# wifi_r3-esp_wr02.net
KiCad netlist of a schematic drawn in EAGLE
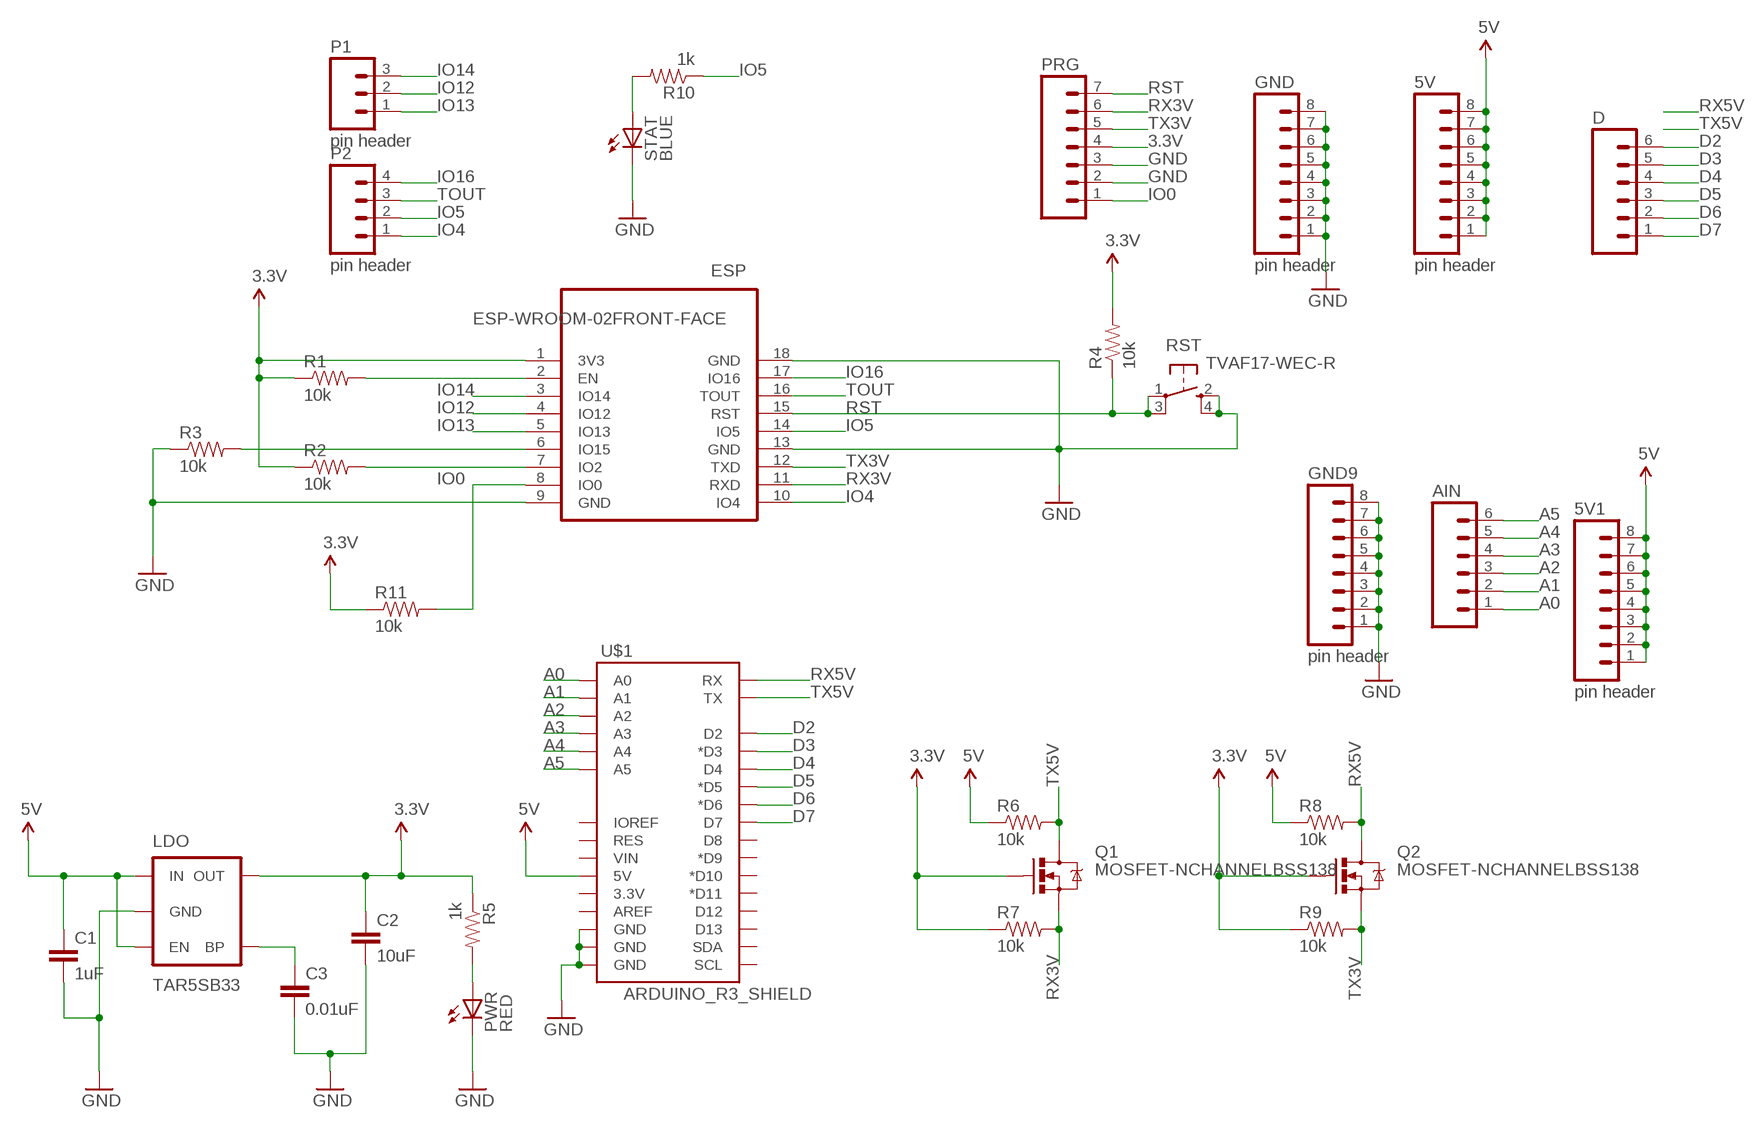
[diagram p0: schematic, sheet 1]

(export (version "E")
  (design (tool "Eeschema 10.0.6"))
  (components
    (comp (ref "5V")
      (value "pin header")
      (footprint "eagle-import:1X08")
      (libsource (lib "eagle-import") (part "M081X08"))
    )
    (comp (ref "5V1")
      (value "pin header")
      (footprint "eagle-import:1X08")
      (libsource (lib "eagle-import") (part "M081X08"))
    )
    (comp (ref "AIN")
      (value "M06SIP")
      (footprint "eagle-import:1X06")
      (libsource (lib "eagle-import") (part "M06SIP"))
    )
    (comp (ref "C1")
      (value "1uF")
      (footprint "eagle-import:0603-CAP")
      (libsource (lib "eagle-import") (part "CAP0603-CAP"))
    )
    (comp (ref "C2")
      (value "10uF")
      (footprint "eagle-import:0805")
      (libsource (lib "eagle-import") (part "CAP0805"))
    )
    (comp (ref "C3")
      (value "0.01uF")
      (footprint "eagle-import:0603-CAP")
      (libsource (lib "eagle-import") (part "CAP0603-CAP"))
    )
    (comp (ref "D")
      (value "M06SIP")
      (footprint "eagle-import:1X06")
      (libsource (lib "eagle-import") (part "M06SIP"))
    )
    (comp (ref "ESP")
      (value "ESP-WROOM-02FRONT-FACE")
      (footprint "eagle-import:FRONT-FACE")
      (libsource (lib "eagle-import") (part "ESP-WROOM-02FRONT-FACE"))
    )
    (comp (ref "GND")
      (value "pin header")
      (footprint "eagle-import:1X08")
      (libsource (lib "eagle-import") (part "M081X08"))
    )
    (comp (ref "GND9")
      (value "pin header")
      (footprint "eagle-import:1X08")
      (libsource (lib "eagle-import") (part "M081X08"))
    )
    (comp (ref "LDO")
      (value "TAR5SB33")
      (footprint "eagle-import:SOT23-5")
      (libsource (lib "eagle-import") (part "TAR5SB33"))
    )
    (comp (ref "P1")
      (value "pin header")
      (footprint "eagle-import:1X03")
      (libsource (lib "eagle-import") (part "M03PTH"))
    )
    (comp (ref "P2")
      (value "pin header")
      (footprint "eagle-import:1X04")
      (libsource (lib "eagle-import") (part "M04PTH"))
    )
    (comp (ref "PRG")
      (value "M07")
      (footprint "eagle-import:1X07")
      (libsource (lib "eagle-import") (part "M07"))
    )
    (comp (ref "PWR")
      (value "RED")
      (footprint "eagle-import:LED-0603")
      (libsource (lib "eagle-import") (part "LED0603"))
    )
    (comp (ref "Q1")
      (value "MOSFET-NCHANNELBSS138")
      (footprint "eagle-import:SOT23")
      (libsource (lib "eagle-import") (part "MOSFET-NCHANNELBSS138"))
    )
    (comp (ref "Q2")
      (value "MOSFET-NCHANNELBSS138")
      (footprint "eagle-import:SOT23")
      (libsource (lib "eagle-import") (part "MOSFET-NCHANNELBSS138"))
    )
    (comp (ref "R1")
      (value "10k")
      (footprint "eagle-import:0603-RES")
      (libsource (lib "eagle-import") (part "RESISTOR0603"))
    )
    (comp (ref "R2")
      (value "10k")
      (footprint "eagle-import:0603-RES")
      (libsource (lib "eagle-import") (part "RESISTOR0603"))
    )
    (comp (ref "R3")
      (value "10k")
      (footprint "eagle-import:0603-RES")
      (libsource (lib "eagle-import") (part "RESISTOR0603"))
    )
    (comp (ref "R4")
      (value "10k")
      (footprint "eagle-import:0603-RES")
      (libsource (lib "eagle-import") (part "RESISTOR0603"))
    )
    (comp (ref "R5")
      (value "1k")
      (footprint "eagle-import:0603-RES")
      (libsource (lib "eagle-import") (part "RESISTOR0603"))
    )
    (comp (ref "R6")
      (value "10k")
      (footprint "eagle-import:0603-RES")
      (libsource (lib "eagle-import") (part "RESISTOR0603"))
    )
    (comp (ref "R7")
      (value "10k")
      (footprint "eagle-import:0603-RES")
      (libsource (lib "eagle-import") (part "RESISTOR0603"))
    )
    (comp (ref "R8")
      (value "10k")
      (footprint "eagle-import:0603-RES")
      (libsource (lib "eagle-import") (part "RESISTOR0603"))
    )
    (comp (ref "R9")
      (value "10k")
      (footprint "eagle-import:0603-RES")
      (libsource (lib "eagle-import") (part "RESISTOR0603"))
    )
    (comp (ref "R10")
      (value "1k")
      (footprint "eagle-import:0603-RES")
      (libsource (lib "eagle-import") (part "RESISTOR0603"))
    )
    (comp (ref "R11")
      (value "10k")
      (footprint "eagle-import:0603-RES")
      (libsource (lib "eagle-import") (part "RESISTOR0603"))
    )
    (comp (ref "RST")
      (value "TVAF17-WEC-R")
      (footprint "eagle-import:KMR2")
      (libsource (lib "eagle-import") (part "SPST_TACT-KMR2"))
    )
    (comp (ref "STAT")
      (value "BLUE")
      (footprint "eagle-import:LED-0603")
      (libsource (lib "eagle-import") (part "LED0603"))
    )
    (comp (ref "U$1")
      (value "ARDUINO_R3_SHIELD")
      (footprint "eagle-import:UNO_R3_SHIELD")
      (libsource (lib "eagle-import") (part "ARDUINO_R3_SHIELD"))
    )
  )
  (nets
    (net (code "1") (name "/A0") (class "Default")
      (node (ref "AIN") (pin "1") (pinfunction "1_1") (pintype "passive"))
      (node (ref "U$1") (pin "A0") (pinfunction "A0_A0") (pintype "bidirectional"))
    )
    (net (code "2") (name "/A1") (class "Default")
      (node (ref "AIN") (pin "2") (pinfunction "2_2") (pintype "passive"))
      (node (ref "U$1") (pin "A1") (pinfunction "A1_A1") (pintype "bidirectional"))
    )
    (net (code "3") (name "/A2") (class "Default")
      (node (ref "AIN") (pin "3") (pinfunction "3_3") (pintype "passive"))
      (node (ref "U$1") (pin "A2") (pinfunction "A2_A2") (pintype "bidirectional"))
    )
    (net (code "4") (name "/A3") (class "Default")
      (node (ref "AIN") (pin "4") (pinfunction "4_4") (pintype "passive"))
      (node (ref "U$1") (pin "A3") (pinfunction "A3_A3") (pintype "bidirectional"))
    )
    (net (code "5") (name "/A4") (class "Default")
      (node (ref "AIN") (pin "5") (pinfunction "5_5") (pintype "passive"))
      (node (ref "U$1") (pin "A4") (pinfunction "A4_A4") (pintype "bidirectional"))
    )
    (net (code "6") (name "/A5") (class "Default")
      (node (ref "AIN") (pin "6") (pinfunction "6_6") (pintype "passive"))
      (node (ref "U$1") (pin "A5") (pinfunction "A5_A5") (pintype "bidirectional"))
    )
    (net (code "7") (name "/D2") (class "Default")
      (node (ref "D") (pin "6") (pinfunction "6_6") (pintype "passive"))
      (node (ref "U$1") (pin "D2") (pinfunction "D2_D2") (pintype "bidirectional"))
    )
    (net (code "8") (name "/D3") (class "Default")
      (node (ref "D") (pin "5") (pinfunction "5_5") (pintype "passive"))
      (node (ref "U$1") (pin "D3") (pinfunction "*D3_D3") (pintype "bidirectional"))
    )
    (net (code "9") (name "/D4") (class "Default")
      (node (ref "D") (pin "4") (pinfunction "4_4") (pintype "passive"))
      (node (ref "U$1") (pin "D4") (pinfunction "D4_D4") (pintype "bidirectional"))
    )
    (net (code "10") (name "/D5") (class "Default")
      (node (ref "D") (pin "3") (pinfunction "3_3") (pintype "passive"))
      (node (ref "U$1") (pin "D5") (pinfunction "*D5_D5") (pintype "bidirectional"))
    )
    (net (code "11") (name "/D6") (class "Default")
      (node (ref "D") (pin "2") (pinfunction "2_2") (pintype "passive"))
      (node (ref "U$1") (pin "D6") (pinfunction "*D6_D6") (pintype "bidirectional"))
    )
    (net (code "12") (name "/D7") (class "Default")
      (node (ref "D") (pin "1") (pinfunction "1_1") (pintype "passive"))
      (node (ref "U$1") (pin "D7") (pinfunction "D7_D7") (pintype "bidirectional"))
    )
    (net (code "13") (name "/IO0") (class "Default")
      (node (ref "ESP") (pin "8") (pinfunction "IO0_8") (pintype "bidirectional"))
      (node (ref "PRG") (pin "1") (pinfunction "1_1") (pintype "passive"))
      (node (ref "R11") (pin "2") (pinfunction "2_2") (pintype "passive"))
    )
    (net (code "14") (name "/IO4") (class "Default")
      (node (ref "ESP") (pin "10") (pinfunction "IO4_10") (pintype "bidirectional"))
      (node (ref "P2") (pin "1") (pinfunction "1_1") (pintype "passive"))
    )
    (net (code "15") (name "/IO5") (class "Default")
      (node (ref "ESP") (pin "14") (pinfunction "IO5_14") (pintype "open_collector"))
      (node (ref "P2") (pin "2") (pinfunction "2_2") (pintype "passive"))
      (node (ref "R10") (pin "1") (pinfunction "1_1") (pintype "passive"))
    )
    (net (code "16") (name "/IO12") (class "Default")
      (node (ref "ESP") (pin "4") (pinfunction "IO12_4") (pintype "bidirectional"))
      (node (ref "P1") (pin "2") (pinfunction "2_2") (pintype "passive"))
    )
    (net (code "17") (name "/IO13") (class "Default")
      (node (ref "ESP") (pin "5") (pinfunction "IO13_5") (pintype "bidirectional"))
      (node (ref "P1") (pin "1") (pinfunction "1_1") (pintype "passive"))
    )
    (net (code "18") (name "/IO14") (class "Default")
      (node (ref "ESP") (pin "3") (pinfunction "IO14_3") (pintype "bidirectional"))
      (node (ref "P1") (pin "3") (pinfunction "3_3") (pintype "passive"))
    )
    (net (code "19") (name "/IO16") (class "Default")
      (node (ref "ESP") (pin "17") (pinfunction "IO16_17") (pintype "bidirectional"))
      (node (ref "P2") (pin "4") (pinfunction "4_4") (pintype "passive"))
    )
    (net (code "20") (name "/RST") (class "Default")
      (node (ref "ESP") (pin "15") (pinfunction "RST_15") (pintype "bidirectional"))
      (node (ref "PRG") (pin "7") (pinfunction "7_7") (pintype "passive"))
      (node (ref "R4") (pin "1") (pinfunction "1_1") (pintype "passive"))
      (node (ref "RST") (pin "1") (pinfunction "P_1") (pintype "passive"))
      (node (ref "RST") (pin "3") (pinfunction "P_3") (pintype "passive"))
    )
    (net (code "21") (name "/RX3V") (class "Default")
      (node (ref "ESP") (pin "11") (pinfunction "RXD_11") (pintype "bidirectional"))
      (node (ref "PRG") (pin "6") (pinfunction "6_6") (pintype "passive"))
      (node (ref "Q1") (pin "2") (pinfunction "S_2") (pintype "passive"))
      (node (ref "R7") (pin "2") (pinfunction "2_2") (pintype "passive"))
    )
    (net (code "22") (name "/RX5V") (class "Default")
      (node (ref "Q2") (pin "3") (pinfunction "D_3") (pintype "passive"))
      (node (ref "R8") (pin "2") (pinfunction "2_2") (pintype "passive"))
      (node (ref "U$1") (pin "RX") (pinfunction "RX_RX") (pintype "bidirectional"))
    )
    (net (code "23") (name "/TOUT") (class "Default")
      (node (ref "ESP") (pin "16") (pinfunction "TOUT_16") (pintype "bidirectional"))
      (node (ref "P2") (pin "3") (pinfunction "3_3") (pintype "passive"))
    )
    (net (code "24") (name "/TX3V") (class "Default")
      (node (ref "ESP") (pin "12") (pinfunction "TXD_12") (pintype "bidirectional"))
      (node (ref "PRG") (pin "5") (pinfunction "5_5") (pintype "passive"))
      (node (ref "Q2") (pin "2") (pinfunction "S_2") (pintype "passive"))
      (node (ref "R9") (pin "2") (pinfunction "2_2") (pintype "passive"))
    )
    (net (code "25") (name "/TX5V") (class "Default")
      (node (ref "Q1") (pin "3") (pinfunction "D_3") (pintype "passive"))
      (node (ref "R6") (pin "2") (pinfunction "2_2") (pintype "passive"))
      (node (ref "U$1") (pin "TX") (pinfunction "TX_TX") (pintype "bidirectional"))
    )
    (net (code "26") (name "3.3V") (class "Default")
      (node (ref "C2") (pin "1") (pinfunction "1_1") (pintype "passive"))
      (node (ref "ESP") (pin "1") (pinfunction "3V3_1") (pintype "power_in"))
      (node (ref "LDO") (pin "5") (pinfunction "OUT_5") (pintype "passive"))
      (node (ref "PRG") (pin "4") (pinfunction "4_4") (pintype "passive"))
      (node (ref "Q1") (pin "1") (pinfunction "G_1") (pintype "passive"))
      (node (ref "Q2") (pin "1") (pinfunction "G_1") (pintype "passive"))
      (node (ref "R1") (pin "1") (pinfunction "1_1") (pintype "passive"))
      (node (ref "R11") (pin "1") (pinfunction "1_1") (pintype "passive"))
      (node (ref "R2") (pin "1") (pinfunction "1_1") (pintype "passive"))
      (node (ref "R4") (pin "2") (pinfunction "2_2") (pintype "passive"))
      (node (ref "R5") (pin "1") (pinfunction "1_1") (pintype "passive"))
      (node (ref "R7") (pin "1") (pinfunction "1_1") (pintype "passive"))
      (node (ref "R9") (pin "1") (pinfunction "1_1") (pintype "passive"))
    )
    (net (code "27") (name "5V") (class "Default")
      (node (ref "5V") (pin "1") (pinfunction "1_1") (pintype "passive"))
      (node (ref "5V") (pin "2") (pinfunction "2_2") (pintype "passive"))
      (node (ref "5V") (pin "3") (pinfunction "3_3") (pintype "passive"))
      (node (ref "5V") (pin "4") (pinfunction "4_4") (pintype "passive"))
      (node (ref "5V") (pin "5") (pinfunction "5_5") (pintype "passive"))
      (node (ref "5V") (pin "6") (pinfunction "6_6") (pintype "passive"))
      (node (ref "5V") (pin "7") (pinfunction "7_7") (pintype "passive"))
      (node (ref "5V") (pin "8") (pinfunction "8_8") (pintype "passive"))
      (node (ref "5V1") (pin "1") (pinfunction "1_1") (pintype "passive"))
      (node (ref "5V1") (pin "2") (pinfunction "2_2") (pintype "passive"))
      (node (ref "5V1") (pin "3") (pinfunction "3_3") (pintype "passive"))
      (node (ref "5V1") (pin "4") (pinfunction "4_4") (pintype "passive"))
      (node (ref "5V1") (pin "5") (pinfunction "5_5") (pintype "passive"))
      (node (ref "5V1") (pin "6") (pinfunction "6_6") (pintype "passive"))
      (node (ref "5V1") (pin "7") (pinfunction "7_7") (pintype "passive"))
      (node (ref "5V1") (pin "8") (pinfunction "8_8") (pintype "passive"))
      (node (ref "C1") (pin "1") (pinfunction "1_1") (pintype "passive"))
      (node (ref "LDO") (pin "1") (pinfunction "IN_1") (pintype "input"))
      (node (ref "LDO") (pin "3") (pinfunction "EN_3") (pintype "input"))
      (node (ref "R6") (pin "1") (pinfunction "1_1") (pintype "passive"))
      (node (ref "R8") (pin "1") (pinfunction "1_1") (pintype "passive"))
      (node (ref "U$1") (pin "5V") (pinfunction "5V_5V") (pintype "bidirectional"))
    )
    (net (code "28") (name "GND") (class "Default")
      (node (ref "C1") (pin "2") (pinfunction "2_2") (pintype "passive"))
      (node (ref "C2") (pin "2") (pinfunction "2_2") (pintype "passive"))
      (node (ref "C3") (pin "2") (pinfunction "2_2") (pintype "passive"))
      (node (ref "ESP") (pin "13") (pinfunction "GND_13") (pintype "power_in"))
      (node (ref "ESP") (pin "18") (pinfunction "GND_18") (pintype "power_in"))
      (node (ref "ESP") (pin "9") (pinfunction "GND_9") (pintype "power_in"))
      (node (ref "GND") (pin "1") (pinfunction "1_1") (pintype "passive"))
      (node (ref "GND") (pin "2") (pinfunction "2_2") (pintype "passive"))
      (node (ref "GND") (pin "3") (pinfunction "3_3") (pintype "passive"))
      (node (ref "GND") (pin "4") (pinfunction "4_4") (pintype "passive"))
      (node (ref "GND") (pin "5") (pinfunction "5_5") (pintype "passive"))
      (node (ref "GND") (pin "6") (pinfunction "6_6") (pintype "passive"))
      (node (ref "GND") (pin "7") (pinfunction "7_7") (pintype "passive"))
      (node (ref "GND") (pin "8") (pinfunction "8_8") (pintype "passive"))
      (node (ref "GND9") (pin "1") (pinfunction "1_1") (pintype "passive"))
      (node (ref "GND9") (pin "2") (pinfunction "2_2") (pintype "passive"))
      (node (ref "GND9") (pin "3") (pinfunction "3_3") (pintype "passive"))
      (node (ref "GND9") (pin "4") (pinfunction "4_4") (pintype "passive"))
      (node (ref "GND9") (pin "5") (pinfunction "5_5") (pintype "passive"))
      (node (ref "GND9") (pin "6") (pinfunction "6_6") (pintype "passive"))
      (node (ref "GND9") (pin "7") (pinfunction "7_7") (pintype "passive"))
      (node (ref "GND9") (pin "8") (pinfunction "8_8") (pintype "passive"))
      (node (ref "LDO") (pin "2") (pinfunction "GND_2") (pintype "input"))
      (node (ref "PRG") (pin "2") (pinfunction "2_2") (pintype "passive"))
      (node (ref "PRG") (pin "3") (pinfunction "3_3") (pintype "passive"))
      (node (ref "PWR") (pin "C") (pinfunction "C_C") (pintype "passive"))
      (node (ref "R3") (pin "1") (pinfunction "1_1") (pintype "passive"))
      (node (ref "RST") (pin "2") (pinfunction "S_2") (pintype "passive"))
      (node (ref "RST") (pin "4") (pinfunction "S_4") (pintype "passive"))
      (node (ref "STAT") (pin "C") (pinfunction "C_C") (pintype "passive"))
      (node (ref "U$1") (pin "GND@0") (pinfunction "GND_GND@0") (pintype "bidirectional"))
      (node (ref "U$1") (pin "GND@1") (pinfunction "GND_GND@1") (pintype "bidirectional"))
      (node (ref "U$1") (pin "GND@2") (pinfunction "GND_GND@2") (pintype "bidirectional"))
    )
    (net (code "29") (name "Net-(ESP-EN)") (class "Default")
      (node (ref "ESP") (pin "2") (pinfunction "EN_2") (pintype "bidirectional"))
      (node (ref "R1") (pin "2") (pinfunction "2_2") (pintype "passive"))
    )
    (net (code "30") (name "Net-(ESP-IO2)") (class "Default")
      (node (ref "ESP") (pin "7") (pinfunction "IO2_7") (pintype "bidirectional"))
      (node (ref "R2") (pin "2") (pinfunction "2_2") (pintype "passive"))
    )
    (net (code "31") (name "Net-(ESP-IO15)") (class "Default")
      (node (ref "ESP") (pin "6") (pinfunction "IO15_6") (pintype "bidirectional"))
      (node (ref "R3") (pin "2") (pinfunction "2_2") (pintype "passive"))
    )
    (net (code "32") (name "Net-(LDO-BP)") (class "Default")
      (node (ref "C3") (pin "1") (pinfunction "1_1") (pintype "passive"))
      (node (ref "LDO") (pin "4") (pinfunction "BP_4") (pintype "input"))
    )
    (net (code "33") (name "Net-(PWR-PadA)") (class "Default")
      (node (ref "PWR") (pin "A") (pinfunction "A_A") (pintype "passive"))
      (node (ref "R5") (pin "2") (pinfunction "2_2") (pintype "passive"))
    )
    (net (code "34") (name "Net-(R10-Pad2)") (class "Default")
      (node (ref "R10") (pin "2") (pinfunction "2_2") (pintype "passive"))
      (node (ref "STAT") (pin "A") (pinfunction "A_A") (pintype "passive"))
    )
    (net (code "35") (name "unconnected-(U$1-*D9-PadD9)") (class "Default")
      (node (ref "U$1") (pin "D9") (pinfunction "*D9_D9") (pintype "bidirectional"))
    )
    (net (code "36") (name "unconnected-(U$1-*D10-PadD10)") (class "Default")
      (node (ref "U$1") (pin "D10") (pinfunction "*D10_D10") (pintype "bidirectional"))
    )
    (net (code "37") (name "unconnected-(U$1-*D11-PadD11)") (class "Default")
      (node (ref "U$1") (pin "D11") (pinfunction "*D11_D11") (pintype "bidirectional"))
    )
    (net (code "38") (name "unconnected-(U$1-Pad3.3V)") (class "Default")
      (node (ref "U$1") (pin "3.3V") (pinfunction "3.3V_3.3V") (pintype "bidirectional"))
    )
    (net (code "39") (name "unconnected-(U$1-PadAREF)") (class "Default")
      (node (ref "U$1") (pin "AREF") (pinfunction "AREF_AREF") (pintype "bidirectional"))
    )
    (net (code "40") (name "unconnected-(U$1-PadD8)") (class "Default")
      (node (ref "U$1") (pin "D8") (pinfunction "D8_D8") (pintype "bidirectional"))
    )
    (net (code "41") (name "unconnected-(U$1-PadD12)") (class "Default")
      (node (ref "U$1") (pin "D12") (pinfunction "D12_D12") (pintype "bidirectional"))
    )
    (net (code "42") (name "unconnected-(U$1-PadD13)") (class "Default")
      (node (ref "U$1") (pin "D13") (pinfunction "D13_D13") (pintype "bidirectional"))
    )
    (net (code "43") (name "unconnected-(U$1-PadIOREF)") (class "Default")
      (node (ref "U$1") (pin "IOREF") (pinfunction "IOREF_IOREF") (pintype "bidirectional"))
    )
    (net (code "44") (name "unconnected-(U$1-PadRES)") (class "Default")
      (node (ref "U$1") (pin "RES") (pinfunction "RES_RES") (pintype "bidirectional"))
    )
    (net (code "45") (name "unconnected-(U$1-PadSCL)") (class "Default")
      (node (ref "U$1") (pin "SCL") (pinfunction "SCL_SCL") (pintype "bidirectional"))
    )
    (net (code "46") (name "unconnected-(U$1-PadSDA)") (class "Default")
      (node (ref "U$1") (pin "SDA") (pinfunction "SDA_SDA") (pintype "bidirectional"))
    )
    (net (code "47") (name "unconnected-(U$1-PadVIN)") (class "Default")
      (node (ref "U$1") (pin "VIN") (pinfunction "VIN_VIN") (pintype "bidirectional"))
    )
  )
)
